# main_connector.net
KiCad netlist of a schematic drawn in Altium Designer
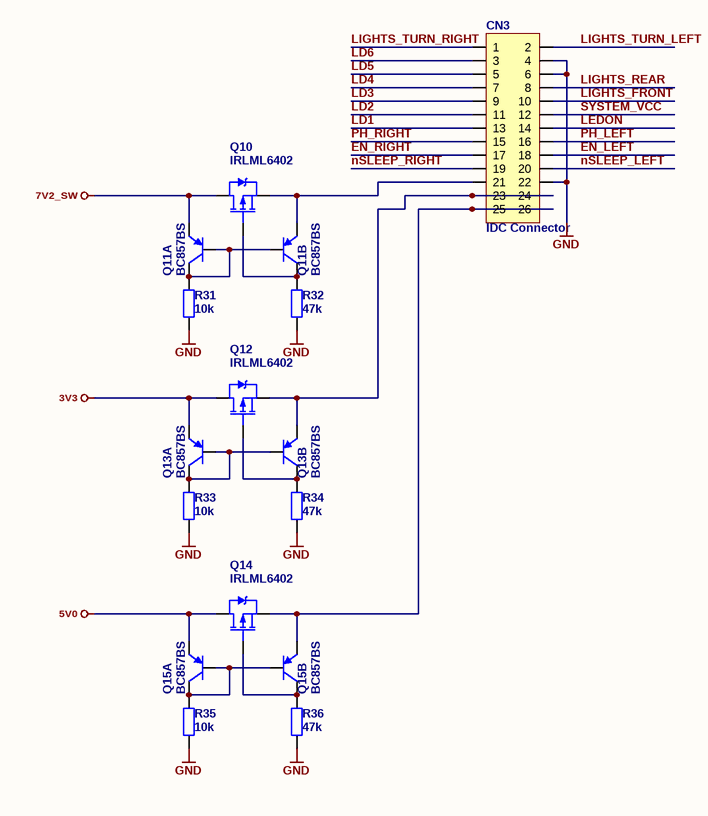
[diagram p0: main_connector.SchDoc]

(export (version "E")
  (design (tool "Eeschema 10.0.6"))
  (components
    (comp (ref "CN3")
      (value "IDC Connector")
      (footprint "IDC26_RA_LONG_W_CN")
      (libsource (lib "idc") (part "CN_13x2"))
    )
    (comp (ref "Q10")
      (value "IRLML6402")
      (footprint "SOT-23")
      (description "P-Channel; -20V, -3.7A, 1.3W; HEXFET Power MOS-FET")
      (libsource (lib "transistors_mos") (part "IRLML6402"))
    )
    (comp (ref "Q11")
      (value "BC857BS")
      (footprint "SOT-323-6 (SOT-363, SC88, SC70-6)")
      (description "2xPNP General Purpose Transistor (VCE=-45V, IC=-100mA)")
      (libsource (lib "transistors_bjt") (part "BC857BS"))
    )
    (comp (ref "Q12")
      (value "IRLML6402")
      (footprint "SOT-23")
      (description "P-Channel; -20V, -3.7A, 1.3W; HEXFET Power MOS-FET")
      (libsource (lib "transistors_mos") (part "IRLML6402"))
    )
    (comp (ref "Q13")
      (value "BC857BS")
      (footprint "SOT-323-6 (SOT-363, SC88, SC70-6)")
      (description "2xPNP General Purpose Transistor (VCE=-45V, IC=-100mA)")
      (libsource (lib "transistors_bjt") (part "BC857BS"))
    )
    (comp (ref "Q14")
      (value "IRLML6402")
      (footprint "SOT-23")
      (description "P-Channel; -20V, -3.7A, 1.3W; HEXFET Power MOS-FET")
      (libsource (lib "transistors_mos") (part "IRLML6402"))
    )
    (comp (ref "Q15")
      (value "BC857BS")
      (footprint "SOT-323-6 (SOT-363, SC88, SC70-6)")
      (description "2xPNP General Purpose Transistor (VCE=-45V, IC=-100mA)")
      (libsource (lib "transistors_bjt") (part "BC857BS"))
    )
    (comp (ref "R31")
      (value "10k")
      (footprint "R0805")
      (description "Resistor")
      (libsource (lib "resistors") (part "Res"))
    )
    (comp (ref "R32")
      (value "47k")
      (footprint "R0805")
      (description "Resistor")
      (libsource (lib "resistors") (part "Res"))
    )
    (comp (ref "R33")
      (value "10k")
      (footprint "R0805")
      (description "Resistor")
      (libsource (lib "resistors") (part "Res"))
    )
    (comp (ref "R34")
      (value "47k")
      (footprint "R0805")
      (description "Resistor")
      (libsource (lib "resistors") (part "Res"))
    )
    (comp (ref "R35")
      (value "10k")
      (footprint "R0805")
      (description "Resistor")
      (libsource (lib "resistors") (part "Res"))
    )
    (comp (ref "R36")
      (value "47k")
      (footprint "R0805")
      (description "Resistor")
      (libsource (lib "resistors") (part "Res"))
    )
  )
  (nets
    (net (code "1") (name "/EN_LEFT") (class "Default")
      (node (ref "CN3") (pin "18") (pinfunction "18_18") (pintype "passive"))
    )
    (net (code "2") (name "/EN_RIGHT") (class "Default")
      (node (ref "CN3") (pin "17") (pinfunction "17_17") (pintype "passive"))
    )
    (net (code "3") (name "/LD1") (class "Default")
      (node (ref "CN3") (pin "13") (pinfunction "13_13") (pintype "passive"))
    )
    (net (code "4") (name "/LD2") (class "Default")
      (node (ref "CN3") (pin "11") (pinfunction "11_11") (pintype "passive"))
    )
    (net (code "5") (name "/LD3") (class "Default")
      (node (ref "CN3") (pin "9") (pinfunction "9_9") (pintype "passive"))
    )
    (net (code "6") (name "/LD4") (class "Default")
      (node (ref "CN3") (pin "7") (pinfunction "7_7") (pintype "passive"))
    )
    (net (code "7") (name "/LD5") (class "Default")
      (node (ref "CN3") (pin "5") (pinfunction "5_5") (pintype "passive"))
    )
    (net (code "8") (name "/LD6") (class "Default")
      (node (ref "CN3") (pin "3") (pinfunction "3_3") (pintype "passive"))
    )
    (net (code "9") (name "/LEDON") (class "Default")
      (node (ref "CN3") (pin "14") (pinfunction "14_14") (pintype "passive"))
    )
    (net (code "10") (name "/LIGHTS_FRONT") (class "Default")
      (node (ref "CN3") (pin "10") (pinfunction "10_10") (pintype "passive"))
    )
    (net (code "11") (name "/LIGHTS_REAR") (class "Default")
      (node (ref "CN3") (pin "8") (pinfunction "8_8") (pintype "passive"))
    )
    (net (code "12") (name "/LIGHTS_TURN_LEFT") (class "Default")
      (node (ref "CN3") (pin "2") (pinfunction "2_2") (pintype "passive"))
    )
    (net (code "13") (name "/LIGHTS_TURN_RIGHT") (class "Default")
      (node (ref "CN3") (pin "1") (pinfunction "1_1") (pintype "passive"))
    )
    (net (code "14") (name "/PH_LEFT") (class "Default")
      (node (ref "CN3") (pin "16") (pinfunction "16_16") (pintype "passive"))
    )
    (net (code "15") (name "/PH_RIGHT") (class "Default")
      (node (ref "CN3") (pin "15") (pinfunction "15_15") (pintype "passive"))
    )
    (net (code "16") (name "/SYSTEM_VCC") (class "Default")
      (node (ref "CN3") (pin "12") (pinfunction "12_12") (pintype "passive"))
    )
    (net (code "17") (name "/nSLEEP_LEFT") (class "Default")
      (node (ref "CN3") (pin "20") (pinfunction "20_20") (pintype "passive"))
    )
    (net (code "18") (name "/nSLEEP_RIGHT") (class "Default")
      (node (ref "CN3") (pin "19") (pinfunction "19_19") (pintype "passive"))
    )
    (net (code "19") (name "3V3") (class "Default")
      (node (ref "Q12") (pin "3") (pinfunction "D_3") (pintype "passive"))
      (node (ref "Q13") (pin "1") (pinfunction "EA_1") (pintype "passive"))
    )
    (net (code "20") (name "5V0") (class "Default")
      (node (ref "Q14") (pin "3") (pinfunction "D_3") (pintype "passive"))
      (node (ref "Q15") (pin "1") (pinfunction "EA_1") (pintype "passive"))
    )
    (net (code "21") (name "7V2_SW") (class "Default")
      (node (ref "Q10") (pin "3") (pinfunction "D_3") (pintype "passive"))
      (node (ref "Q11") (pin "1") (pinfunction "EA_1") (pintype "passive"))
    )
    (net (code "22") (name "GND") (class "Default")
      (node (ref "CN3") (pin "22") (pinfunction "22_22") (pintype "passive"))
      (node (ref "CN3") (pin "4") (pinfunction "4_4") (pintype "passive"))
      (node (ref "CN3") (pin "6") (pinfunction "6_6") (pintype "passive"))
      (node (ref "R31") (pin "1") (pinfunction "1_1") (pintype "passive"))
      (node (ref "R32") (pin "1") (pinfunction "1_1") (pintype "passive"))
      (node (ref "R33") (pin "1") (pinfunction "1_1") (pintype "passive"))
      (node (ref "R34") (pin "1") (pinfunction "1_1") (pintype "passive"))
      (node (ref "R35") (pin "1") (pinfunction "1_1") (pintype "passive"))
      (node (ref "R36") (pin "1") (pinfunction "1_1") (pintype "passive"))
    )
    (net (code "23") (name "Net-(Q10-G)") (class "Default")
      (node (ref "Q10") (pin "1") (pinfunction "G_1") (pintype "passive"))
      (node (ref "Q11") (pin "3") (pinfunction "CB_3") (pintype "passive"))
      (node (ref "R32") (pin "2") (pinfunction "2_2") (pintype "passive"))
    )
    (net (code "24") (name "Net-(Q10-S)") (class "Default")
      (node (ref "CN3") (pin "21") (pinfunction "21_21") (pintype "passive"))
      (node (ref "Q10") (pin "2") (pinfunction "S_2") (pintype "passive"))
      (node (ref "Q11") (pin "4") (pinfunction "EB_4") (pintype "passive"))
    )
    (net (code "25") (name "Net-(Q11A-BA)") (class "Default")
      (node (ref "Q11") (pin "2") (pinfunction "BA_2") (pintype "passive"))
      (node (ref "Q11") (pin "5") (pinfunction "BB_5") (pintype "passive"))
      (node (ref "Q11") (pin "6") (pinfunction "CA_6") (pintype "passive"))
      (node (ref "R31") (pin "2") (pinfunction "2_2") (pintype "passive"))
    )
    (net (code "26") (name "Net-(Q12-G)") (class "Default")
      (node (ref "Q12") (pin "1") (pinfunction "G_1") (pintype "passive"))
      (node (ref "Q13") (pin "3") (pinfunction "CB_3") (pintype "passive"))
      (node (ref "R34") (pin "2") (pinfunction "2_2") (pintype "passive"))
    )
    (net (code "27") (name "Net-(Q12-S)") (class "Default")
      (node (ref "CN3") (pin "23") (pinfunction "23_23") (pintype "passive"))
      (node (ref "CN3") (pin "24") (pinfunction "24_24") (pintype "passive"))
      (node (ref "Q12") (pin "2") (pinfunction "S_2") (pintype "passive"))
      (node (ref "Q13") (pin "4") (pinfunction "EB_4") (pintype "passive"))
    )
    (net (code "28") (name "Net-(Q13A-BA)") (class "Default")
      (node (ref "Q13") (pin "2") (pinfunction "BA_2") (pintype "passive"))
      (node (ref "Q13") (pin "5") (pinfunction "BB_5") (pintype "passive"))
      (node (ref "Q13") (pin "6") (pinfunction "CA_6") (pintype "passive"))
      (node (ref "R33") (pin "2") (pinfunction "2_2") (pintype "passive"))
    )
    (net (code "29") (name "Net-(Q14-G)") (class "Default")
      (node (ref "Q14") (pin "1") (pinfunction "G_1") (pintype "passive"))
      (node (ref "Q15") (pin "3") (pinfunction "CB_3") (pintype "passive"))
      (node (ref "R36") (pin "2") (pinfunction "2_2") (pintype "passive"))
    )
    (net (code "30") (name "Net-(Q14-S)") (class "Default")
      (node (ref "CN3") (pin "25") (pinfunction "25_25") (pintype "passive"))
      (node (ref "CN3") (pin "26") (pinfunction "26_26") (pintype "passive"))
      (node (ref "Q14") (pin "2") (pinfunction "S_2") (pintype "passive"))
      (node (ref "Q15") (pin "4") (pinfunction "EB_4") (pintype "passive"))
    )
    (net (code "31") (name "Net-(Q15A-BA)") (class "Default")
      (node (ref "Q15") (pin "2") (pinfunction "BA_2") (pintype "passive"))
      (node (ref "Q15") (pin "5") (pinfunction "BB_5") (pintype "passive"))
      (node (ref "Q15") (pin "6") (pinfunction "CA_6") (pintype "passive"))
      (node (ref "R35") (pin "2") (pinfunction "2_2") (pintype "passive"))
    )
  )
)
